# Display.net
KiCad netlist of a schematic drawn in Altium Designer
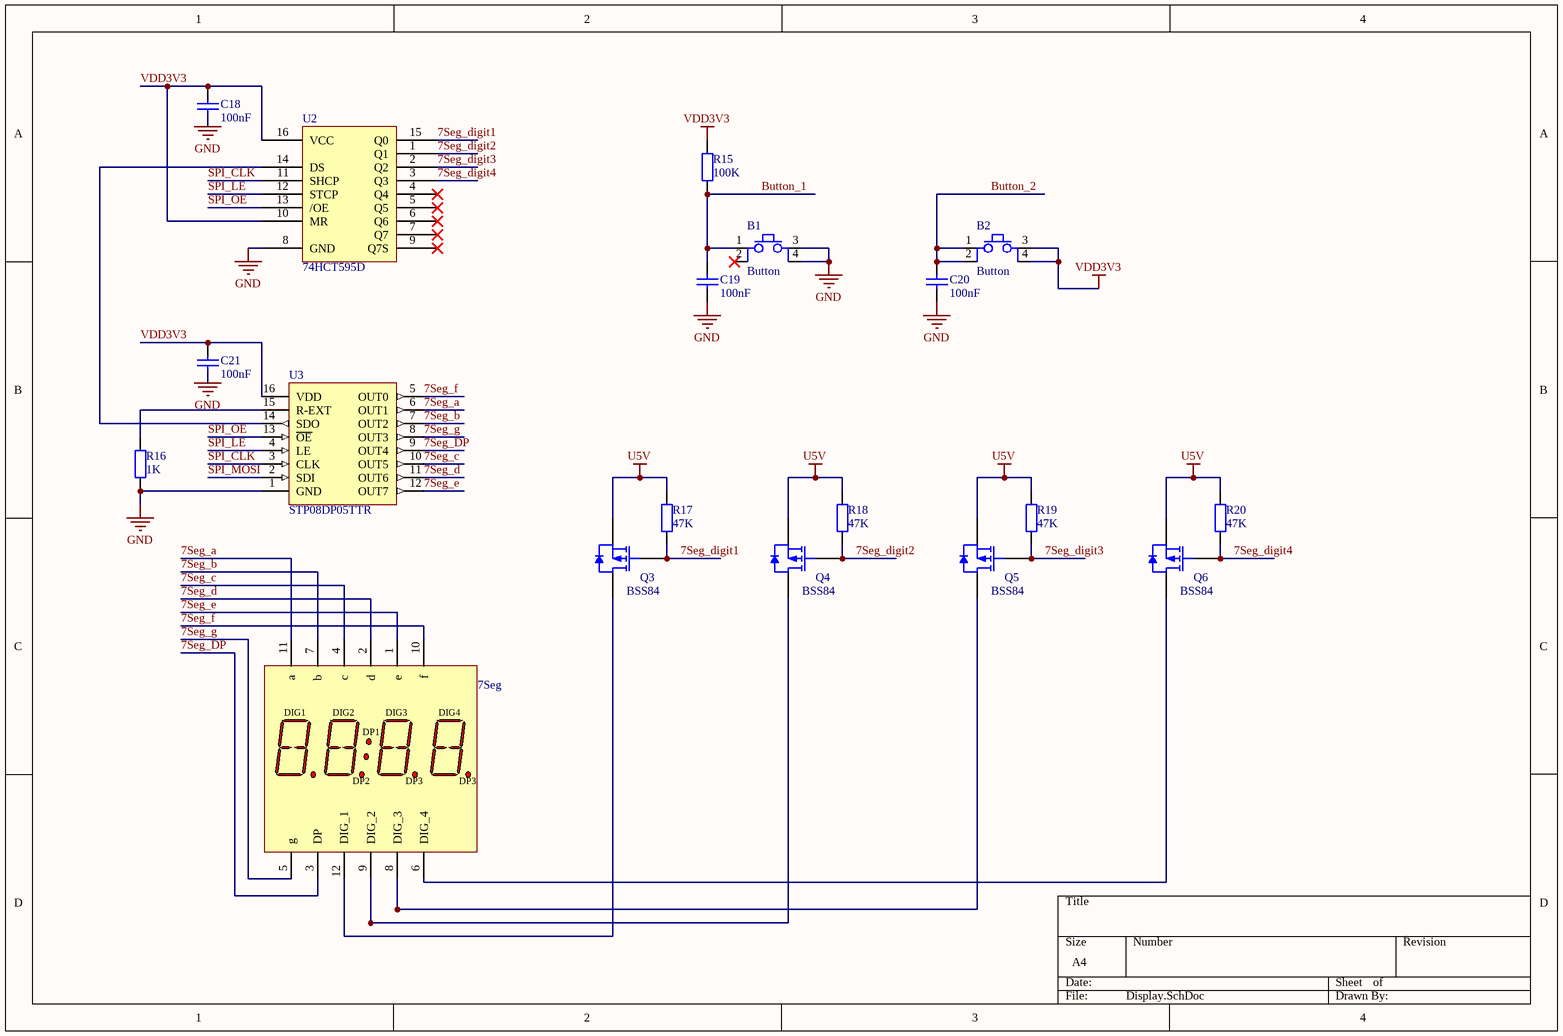
[diagram p0: Display.SchDoc]

(export (version "E")
  (design (tool "Eeschema 10.0.6"))
  (components
    (comp (ref "7Seg")
      (value "4 digit, 12 pin")
      (footprint "7SEG-12pin")
      (libsource (lib "Keep_Talking") (part "7SEG_4Digit_12pin"))
    )
    (comp (ref "B1")
      (value "Button")
      (footprint "FP_BTN_SMD")
      (description "Push button")
      (libsource (lib "hallglib") (part "Button"))
    )
    (comp (ref "B2")
      (value "Button")
      (footprint "FP_BTN_SMD")
      (description "Push button")
      (libsource (lib "hallglib") (part "Button"))
    )
    (comp (ref "C18")
      (value "100nF")
      (footprint "FP_0805_CAP_085")
      (description "Capacitor")
      (fields (field (name "TOLERANCE") "+80%/-20%") (field (name "VOLTAGE") "25V"))
      (libsource (lib "onlablib") (part "CAP 100nF"))
    )
    (comp (ref "C19")
      (value "100nF")
      (footprint "FP_0805_CAP_085")
      (description "Capacitor")
      (fields (field (name "TOLERANCE") "+80%/-20%") (field (name "VOLTAGE") "25V"))
      (libsource (lib "hallglib") (part "CAP 100nF"))
    )
    (comp (ref "C20")
      (value "100nF")
      (footprint "FP_0805_CAP_085")
      (description "Capacitor")
      (fields (field (name "TOLERANCE") "+80%/-20%") (field (name "VOLTAGE") "25V"))
      (libsource (lib "hallglib") (part "CAP 100nF"))
    )
    (comp (ref "C21")
      (value "100nF")
      (footprint "FP_0805_CAP_085")
      (description "Capacitor")
      (fields (field (name "TOLERANCE") "+80%/-20%") (field (name "VOLTAGE") "25V"))
      (libsource (lib "onlablib") (part "CAP 100nF"))
    )
    (comp (ref "Q3")
      (value "BSS84")
      (footprint "SOT23_N")
      (description "P-channel Enhancement Mode Vertical D-MOSFET")
      (libsource (lib "onlablib") (part "BSS84"))
    )
    (comp (ref "Q4")
      (value "BSS84")
      (footprint "SOT23_N")
      (description "P-channel Enhancement Mode Vertical D-MOSFET")
      (libsource (lib "onlablib") (part "BSS84"))
    )
    (comp (ref "Q5")
      (value "BSS84")
      (footprint "SOT23_N")
      (description "P-channel Enhancement Mode Vertical D-MOSFET")
      (libsource (lib "onlablib") (part "BSS84"))
    )
    (comp (ref "Q6")
      (value "BSS84")
      (footprint "SOT23_N")
      (description "P-channel Enhancement Mode Vertical D-MOSFET")
      (libsource (lib "onlablib") (part "BSS84"))
    )
    (comp (ref "R15")
      (value "100K")
      (footprint "FP_0805_RES")
      (description "Resistor")
      (fields (field (name "TOLERANCE") "5%") (field (name "POWER") "125mW"))
      (libsource (lib "hallglib") (part "RES 100K"))
    )
    (comp (ref "R16")
      (value "1K")
      (footprint "FP_0805_RES")
      (description "Resistor")
      (fields (field (name "TOLERANCE") "5%") (field (name "POWER") "125mW"))
      (libsource (lib "onlablib") (part "RES 1K"))
    )
    (comp (ref "R17")
      (value "47K")
      (footprint "FP_0805_RES")
      (description "Resistor")
      (fields (field (name "TOLERANCE") "5%") (field (name "POWER") "125mW"))
      (libsource (lib "onlablib") (part "RES 47K"))
    )
    (comp (ref "R18")
      (value "47K")
      (footprint "FP_0805_RES")
      (description "Resistor")
      (fields (field (name "TOLERANCE") "5%") (field (name "POWER") "125mW"))
      (libsource (lib "onlablib") (part "RES 47K"))
    )
    (comp (ref "R19")
      (value "47K")
      (footprint "FP_0805_RES")
      (description "Resistor")
      (fields (field (name "TOLERANCE") "5%") (field (name "POWER") "125mW"))
      (libsource (lib "onlablib") (part "RES 47K"))
    )
    (comp (ref "R20")
      (value "47K")
      (footprint "FP_0805_RES")
      (description "Resistor")
      (fields (field (name "TOLERANCE") "5%") (field (name "POWER") "125mW"))
      (libsource (lib "onlablib") (part "RES 47K"))
    )
    (comp (ref "U2")
      (value "74HCT595D")
      (footprint "SOP127P600X175-16M")
      (libsource (lib "onlablib") (part "74HCT595D"))
    )
    (comp (ref "U3")
      (value "STP08DP05TTR")
      (footprint "TSOP65P640X120-16M")
      (description "Low voltage, low current power 8-bit shift register")
      (libsource (lib "onlablib") (part "STP08DP05TTR"))
    )
  )
  (nets
    (net (code "1") (name "/7Seg_DP") (class "Default")
      (node (ref "7Seg") (pin "3") (pinfunction "DP_3") (pintype "passive"))
      (node (ref "U3") (pin "9") (pinfunction "OUT4_9") (pintype "output"))
    )
    (net (code "2") (name "/7Seg_a") (class "Default")
      (node (ref "7Seg") (pin "11") (pinfunction "a_11") (pintype "passive"))
      (node (ref "U3") (pin "6") (pinfunction "OUT1_6") (pintype "output"))
    )
    (net (code "3") (name "/7Seg_b") (class "Default")
      (node (ref "7Seg") (pin "7") (pinfunction "b_7") (pintype "passive"))
      (node (ref "U3") (pin "7") (pinfunction "OUT2_7") (pintype "output"))
    )
    (net (code "4") (name "/7Seg_c") (class "Default")
      (node (ref "7Seg") (pin "4") (pinfunction "c_4") (pintype "passive"))
      (node (ref "U3") (pin "10") (pinfunction "OUT5_10") (pintype "output"))
    )
    (net (code "5") (name "/7Seg_d") (class "Default")
      (node (ref "7Seg") (pin "2") (pinfunction "d_2") (pintype "passive"))
      (node (ref "U3") (pin "11") (pinfunction "OUT6_11") (pintype "output"))
    )
    (net (code "6") (name "/7Seg_digit1") (class "Default")
      (node (ref "Q3") (pin "1") (pinfunction "G_1") (pintype "passive"))
      (node (ref "R17") (pin "1") (pinfunction "1_1") (pintype "passive"))
      (node (ref "U2") (pin "15") (pinfunction "Q0_15") (pintype "passive"))
    )
    (net (code "7") (name "/7Seg_digit2") (class "Default")
      (node (ref "Q4") (pin "1") (pinfunction "G_1") (pintype "passive"))
      (node (ref "R18") (pin "1") (pinfunction "1_1") (pintype "passive"))
      (node (ref "U2") (pin "1") (pinfunction "Q1_1") (pintype "passive"))
    )
    (net (code "8") (name "/7Seg_digit3") (class "Default")
      (node (ref "Q5") (pin "1") (pinfunction "G_1") (pintype "passive"))
      (node (ref "R19") (pin "1") (pinfunction "1_1") (pintype "passive"))
      (node (ref "U2") (pin "2") (pinfunction "Q2_2") (pintype "passive"))
    )
    (net (code "9") (name "/7Seg_digit4") (class "Default")
      (node (ref "Q6") (pin "1") (pinfunction "G_1") (pintype "passive"))
      (node (ref "R20") (pin "1") (pinfunction "1_1") (pintype "passive"))
      (node (ref "U2") (pin "3") (pinfunction "Q3_3") (pintype "passive"))
    )
    (net (code "10") (name "/7Seg_e") (class "Default")
      (node (ref "7Seg") (pin "1") (pinfunction "e_1") (pintype "passive"))
      (node (ref "U3") (pin "12") (pinfunction "OUT7_12") (pintype "output"))
    )
    (net (code "11") (name "/7Seg_f") (class "Default")
      (node (ref "7Seg") (pin "10") (pinfunction "f_10") (pintype "passive"))
      (node (ref "U3") (pin "5") (pinfunction "OUT0_5") (pintype "output"))
    )
    (net (code "12") (name "/7Seg_g") (class "Default")
      (node (ref "7Seg") (pin "5") (pinfunction "g_5") (pintype "passive"))
      (node (ref "U3") (pin "8") (pinfunction "OUT3_8") (pintype "output"))
    )
    (net (code "13") (name "/Button_1") (class "Default")
      (node (ref "B1") (pin "1") (pinfunction "1_1") (pintype "passive"))
      (node (ref "C19") (pin "2") (pinfunction "2_2") (pintype "passive"))
      (node (ref "R15") (pin "1") (pinfunction "1_1") (pintype "passive"))
    )
    (net (code "14") (name "/Button_2") (class "Default")
      (node (ref "B2") (pin "1") (pinfunction "1_1") (pintype "passive"))
      (node (ref "B2") (pin "2") (pinfunction "2_2") (pintype "passive"))
      (node (ref "C20") (pin "2") (pinfunction "2_2") (pintype "passive"))
    )
    (net (code "15") (name "/SPI_CLK") (class "Default")
      (node (ref "U2") (pin "11") (pinfunction "SHCP_11") (pintype "passive"))
      (node (ref "U3") (pin "3") (pinfunction "CLK_3") (pintype "input"))
    )
    (net (code "16") (name "/SPI_LE") (class "Default")
      (node (ref "U2") (pin "12") (pinfunction "STCP_12") (pintype "passive"))
      (node (ref "U3") (pin "4") (pinfunction "LE_4") (pintype "input"))
    )
    (net (code "17") (name "/SPI_MOSI") (class "Default")
      (node (ref "U3") (pin "2") (pinfunction "SDI_2") (pintype "input"))
    )
    (net (code "18") (name "/SPI_OE") (class "Default")
      (node (ref "U2") (pin "13") (pinfunction "/OE_13") (pintype "passive"))
      (node (ref "U3") (pin "13") (pinfunction "~{OE}_13") (pintype "input"))
    )
    (net (code "19") (name "GND") (class "Default")
      (node (ref "B1") (pin "3") (pinfunction "3_3") (pintype "passive"))
      (node (ref "B1") (pin "4") (pinfunction "4_4") (pintype "passive"))
      (node (ref "C18") (pin "1") (pinfunction "1_1") (pintype "passive"))
      (node (ref "C19") (pin "1") (pinfunction "1_1") (pintype "passive"))
      (node (ref "C20") (pin "1") (pinfunction "1_1") (pintype "passive"))
      (node (ref "C21") (pin "1") (pinfunction "1_1") (pintype "passive"))
      (node (ref "R16") (pin "1") (pinfunction "1_1") (pintype "passive"))
      (node (ref "U2") (pin "8") (pinfunction "GND_8") (pintype "passive"))
      (node (ref "U3") (pin "1") (pinfunction "GND_1") (pintype "passive"))
    )
    (net (code "20") (name "Net-(7Seg-DIG_1)") (class "Default")
      (node (ref "7Seg") (pin "12") (pinfunction "DIG_1_12") (pintype "passive"))
      (node (ref "Q3") (pin "3") (pinfunction "D_3") (pintype "passive"))
    )
    (net (code "21") (name "Net-(7Seg-DIG_2)") (class "Default")
      (node (ref "7Seg") (pin "9") (pinfunction "DIG_2_9") (pintype "passive"))
      (node (ref "Q4") (pin "3") (pinfunction "D_3") (pintype "passive"))
    )
    (net (code "22") (name "Net-(7Seg-DIG_3)") (class "Default")
      (node (ref "7Seg") (pin "8") (pinfunction "DIG_3_8") (pintype "passive"))
      (node (ref "Q5") (pin "3") (pinfunction "D_3") (pintype "passive"))
    )
    (net (code "23") (name "Net-(7Seg-DIG_4)") (class "Default")
      (node (ref "7Seg") (pin "6") (pinfunction "DIG_4_6") (pintype "passive"))
      (node (ref "Q6") (pin "3") (pinfunction "D_3") (pintype "passive"))
    )
    (net (code "24") (name "Net-(U2-DS)") (class "Default")
      (node (ref "U2") (pin "14") (pinfunction "DS_14") (pintype "passive"))
      (node (ref "U3") (pin "14") (pinfunction "SDO_14") (pintype "output"))
    )
    (net (code "25") (name "Net-(U3-R-EXT)") (class "Default")
      (node (ref "R16") (pin "2") (pinfunction "2_2") (pintype "passive"))
      (node (ref "U3") (pin "15") (pinfunction "R-EXT_15") (pintype "passive"))
    )
    (net (code "26") (name "U5V") (class "Default")
      (node (ref "Q3") (pin "2") (pinfunction "S_2") (pintype "passive"))
      (node (ref "Q4") (pin "2") (pinfunction "S_2") (pintype "passive"))
      (node (ref "Q5") (pin "2") (pinfunction "S_2") (pintype "passive"))
      (node (ref "Q6") (pin "2") (pinfunction "S_2") (pintype "passive"))
      (node (ref "R17") (pin "2") (pinfunction "2_2") (pintype "passive"))
      (node (ref "R18") (pin "2") (pinfunction "2_2") (pintype "passive"))
      (node (ref "R19") (pin "2") (pinfunction "2_2") (pintype "passive"))
      (node (ref "R20") (pin "2") (pinfunction "2_2") (pintype "passive"))
    )
    (net (code "27") (name "VDD3V3") (class "Default")
      (node (ref "B2") (pin "3") (pinfunction "3_3") (pintype "passive"))
      (node (ref "B2") (pin "4") (pinfunction "4_4") (pintype "passive"))
      (node (ref "C18") (pin "2") (pinfunction "2_2") (pintype "passive"))
      (node (ref "C21") (pin "2") (pinfunction "2_2") (pintype "passive"))
      (node (ref "R15") (pin "2") (pinfunction "2_2") (pintype "passive"))
      (node (ref "U2") (pin "10") (pinfunction "MR_10") (pintype "passive"))
      (node (ref "U2") (pin "16") (pinfunction "VCC_16") (pintype "passive"))
      (node (ref "U3") (pin "16") (pinfunction "VDD_16") (pintype "power_in"))
    )
    (net (code "28") (name "unconnected-(B1-Pad2)") (class "Default")
      (node (ref "B1") (pin "2") (pinfunction "2_2") (pintype "passive+no_connect"))
    )
    (net (code "29") (name "unconnected-(U2-Q4-Pad4)") (class "Default")
      (node (ref "U2") (pin "4") (pinfunction "Q4_4") (pintype "passive+no_connect"))
    )
    (net (code "30") (name "unconnected-(U2-Q5-Pad5)") (class "Default")
      (node (ref "U2") (pin "5") (pinfunction "Q5_5") (pintype "passive+no_connect"))
    )
    (net (code "31") (name "unconnected-(U2-Q6-Pad6)") (class "Default")
      (node (ref "U2") (pin "6") (pinfunction "Q6_6") (pintype "passive+no_connect"))
    )
    (net (code "32") (name "unconnected-(U2-Q7-Pad7)") (class "Default")
      (node (ref "U2") (pin "7") (pinfunction "Q7_7") (pintype "passive+no_connect"))
    )
    (net (code "33") (name "unconnected-(U2-Q7S-Pad9)") (class "Default")
      (node (ref "U2") (pin "9") (pinfunction "Q7S_9") (pintype "passive+no_connect"))
    )
  )
)
